# 51.net
KiCad netlist of a schematic drawn in EasyEDA Pro
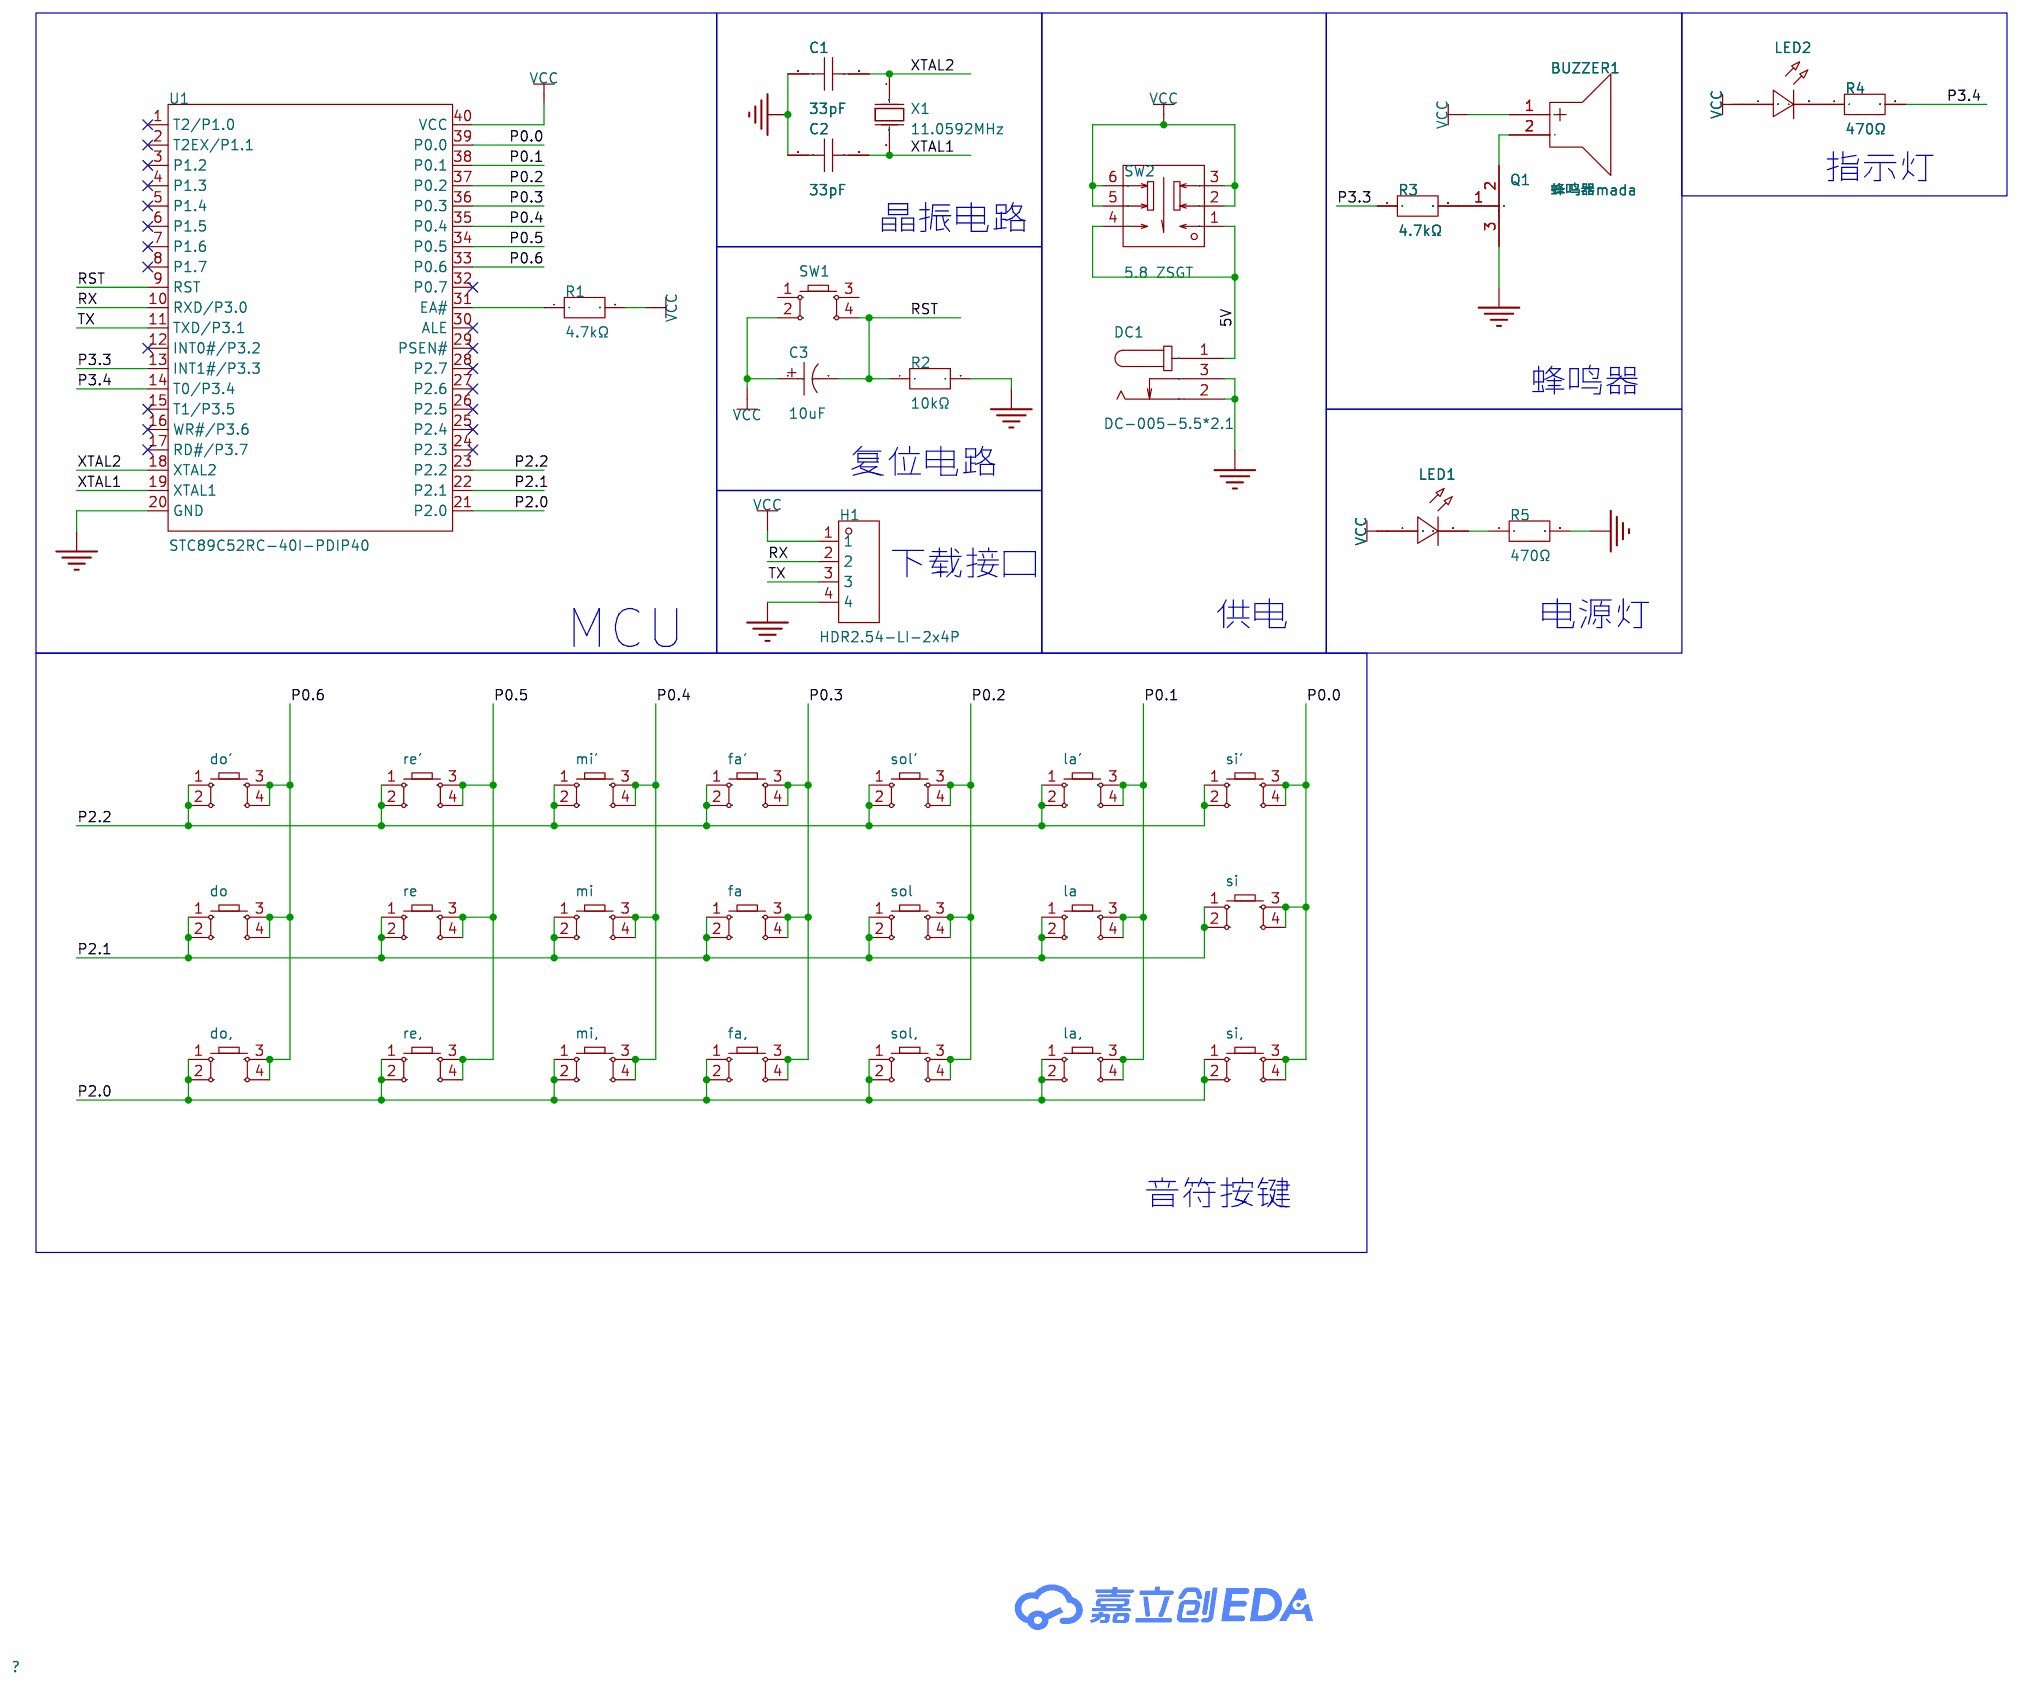
[diagram p0: schematic sheet]

(export (version "E")
  (design (tool "Eeschema 10.0.6"))
  (components
    (comp (ref "BUZZER1")
      (value "蜂鸣器mada")
      (footprint "easyedapro:BUZ-TH_BD9.2-P5.00-D0.6-L-FD")
      (libsource (lib "easyedapro") (part "蜂鸣器MADA"))
    )
    (comp (ref "C1")
      (value "33pF")
      (footprint "easyedapro:CAP-TH_L5.5-W5.0-P5.00-D0.6")
      (description "容值:33pF;精度:±5%;额定电压:2kV;温度系数:SL;")
      (fields (field (name "Manufacturer Part") "CC45SL3DD330JYGNA") (field (name "Manufacturer") "TDK"))
      (libsource (lib "easyedapro") (part "CC45SL3DD330JYGNA"))
    )
    (comp (ref "C2")
      (value "33pF")
      (footprint "easyedapro:CAP-TH_L5.5-W5.0-P5.00-D0.6")
      (description "容值:33pF;精度:±5%;额定电压:2kV;温度系数:SL;")
      (fields (field (name "Manufacturer Part") "CC45SL3DD330JYGNA") (field (name "Manufacturer") "TDK"))
      (libsource (lib "easyedapro") (part "CC45SL3DD330JYGNA"))
    )
    (comp (ref "C3")
      (value "10uF")
      (footprint "easyedapro:CAP-TH_BD5.0-P2.00-D0.5-FD")
      (description "容值:10uF;精度:±20%;额定电压:25V;纹波电流:38mA@120Hz;等效串联电阻(ESR):-;")
      (fields
        (field (name "Manufacturer Part") "KM106M025D11RR0VH2FP0")
        (field (name "Manufacturer") "CX(承兴)")
      )
      (libsource (lib "easyedapro") (part "10uF 25V 5*11"))
    )
    (comp (ref "DC1")
      (value "DC-005-5.5*2.1")
      (footprint "easyedapro:DC-IN-TH_DC-005-2")
      (libsource (lib "easyedapro") (part "DC-005-5.5*2.1"))
    )
    (comp (ref "do")
      (value "~")
      (footprint "easyedapro:Key_SMD_12x12x7.3")
      (libsource (lib "easyedapro") (part "轻触按键"))
    )
    (comp (ref "do'")
      (value "~")
      (footprint "easyedapro:Key_SMD_12x12x7.3")
      (libsource (lib "easyedapro") (part "轻触按键"))
    )
    (comp (ref "do,")
      (value "~")
      (footprint "easyedapro:Key_SMD_12x12x7.3")
      (libsource (lib "easyedapro") (part "轻触按键"))
    )
    (comp (ref "fa")
      (value "~")
      (footprint "easyedapro:Key_SMD_12x12x7.3")
      (libsource (lib "easyedapro") (part "轻触按键"))
    )
    (comp (ref "fa'")
      (value "~")
      (footprint "easyedapro:Key_SMD_12x12x7.3")
      (libsource (lib "easyedapro") (part "轻触按键"))
    )
    (comp (ref "fa,")
      (value "~")
      (footprint "easyedapro:Key_SMD_12x12x7.3")
      (libsource (lib "easyedapro") (part "轻触按键"))
    )
    (comp (ref "H1")
      (value "HDR2.54-LI-2x4P")
      (footprint "easyedapro:HDR-TH_4P-P2.54-V-M")
      (libsource (lib "easyedapro") (part "HDR2.54-LI-2X4P"))
    )
    (comp (ref "la")
      (value "~")
      (footprint "easyedapro:Key_SMD_12x12x7.3")
      (libsource (lib "easyedapro") (part "轻触按键"))
    )
    (comp (ref "la'")
      (value "~")
      (footprint "easyedapro:Key_SMD_12x12x7.3")
      (libsource (lib "easyedapro") (part "轻触按键"))
    )
    (comp (ref "la,")
      (value "~")
      (footprint "easyedapro:Key_SMD_12x12x7.3")
      (libsource (lib "easyedapro") (part "轻触按键"))
    )
    (comp (ref "LED1")
      (value "~")
      (footprint "easyedapro:LED_TH-3mm")
      (libsource (lib "easyedapro") (part "LED_TH-R"))
    )
    (comp (ref "LED2")
      (value "~")
      (footprint "easyedapro:LED_TH-3mm")
      (libsource (lib "easyedapro") (part "LED_TH-R"))
    )
    (comp (ref "mi")
      (value "~")
      (footprint "easyedapro:Key_SMD_12x12x7.3")
      (libsource (lib "easyedapro") (part "轻触按键"))
    )
    (comp (ref "mi'")
      (value "~")
      (footprint "easyedapro:Key_SMD_12x12x7.3")
      (libsource (lib "easyedapro") (part "轻触按键"))
    )
    (comp (ref "mi,")
      (value "~")
      (footprint "easyedapro:Key_SMD_12x12x7.3")
      (libsource (lib "easyedapro") (part "轻触按键"))
    )
    (comp (ref "Q1") (value "~") (footprint "easyedapro:宽三极管") (libsource (lib "easyedapro") (part "宽三极管")))
    (comp (ref "R1")
      (value "4.7kΩ")
      (footprint "easyedapro:RES-TH_BD2.2-L6.5-P10.50-D0.6")
      (description "电阻类型:金属膜电阻;阻值:4.7kΩ;精度:±1%;功率:250mW;温度系数:±50ppm/°C;")
      (fields
        (field (name "Manufacturer Part") "MF0W4FF4701A50")
        (field (name "Manufacturer") "UNI-ROYAL(厚声)")
      )
      (libsource (lib "easyedapro") (part "MF0W4FF4701A50"))
    )
    (comp (ref "R2")
      (value "10kΩ")
      (footprint "easyedapro:RES-TH_BD2.2-L6.5-P10.50-D0.6")
      (description "电阻类型:金属膜电阻;阻值:4.7kΩ;精度:±1%;功率:250mW;温度系数:±50ppm/°C;")
      (fields
        (field (name "Manufacturer Part") "MF0W4FF4701A50")
        (field (name "Manufacturer") "UNI-ROYAL(厚声)")
      )
      (libsource (lib "easyedapro") (part "MF0W4FF4701A50"))
    )
    (comp (ref "R3")
      (value "4.7kΩ")
      (footprint "easyedapro:RES-TH_BD2.2-L6.5-P10.50-D0.6")
      (description "电阻类型:金属膜电阻;阻值:4.7kΩ;精度:±1%;功率:250mW;温度系数:±50ppm/°C;")
      (fields
        (field (name "Manufacturer Part") "MF0W4FF4701A50")
        (field (name "Manufacturer") "UNI-ROYAL(厚声)")
      )
      (libsource (lib "easyedapro") (part "MF0W4FF4701A50"))
    )
    (comp (ref "R4")
      (value "470Ω")
      (footprint "easyedapro:RES-TH_BD2.2-L6.5-P10.50-D0.6")
      (description "电阻类型:金属膜电阻;阻值:470Ω;精度:±1%;功率:250mW;温度系数:±50ppm/°C;")
      (fields
        (field (name "Manufacturer Part") "MF0W4FF4700A50")
        (field (name "Manufacturer") "UNI-ROYAL(厚声)")
      )
      (libsource (lib "easyedapro") (part "MF0W4FF4700A50"))
    )
    (comp (ref "R5")
      (value "470Ω")
      (footprint "easyedapro:RES-TH_BD2.2-L6.5-P10.50-D0.6")
      (description "电阻类型:金属膜电阻;阻值:470Ω;精度:±1%;功率:250mW;温度系数:±50ppm/°C;")
      (fields
        (field (name "Manufacturer Part") "MF0W4FF4700A50")
        (field (name "Manufacturer") "UNI-ROYAL(厚声)")
      )
      (libsource (lib "easyedapro") (part "MF0W4FF4700A50"))
    )
    (comp (ref "re")
      (value "~")
      (footprint "easyedapro:Key_SMD_12x12x7.3")
      (libsource (lib "easyedapro") (part "轻触按键"))
    )
    (comp (ref "re'")
      (value "~")
      (footprint "easyedapro:Key_SMD_12x12x7.3")
      (libsource (lib "easyedapro") (part "轻触按键"))
    )
    (comp (ref "re,")
      (value "~")
      (footprint "easyedapro:Key_SMD_12x12x7.3")
      (libsource (lib "easyedapro") (part "轻触按键"))
    )
    (comp (ref "si")
      (value "~")
      (footprint "easyedapro:Key_SMD_12x12x7.3")
      (libsource (lib "easyedapro") (part "轻触按键"))
    )
    (comp (ref "si'")
      (value "~")
      (footprint "easyedapro:Key_SMD_12x12x7.3")
      (libsource (lib "easyedapro") (part "轻触按键"))
    )
    (comp (ref "si,")
      (value "~")
      (footprint "easyedapro:Key_SMD_12x12x7.3")
      (libsource (lib "easyedapro") (part "轻触按键"))
    )
    (comp (ref "sol")
      (value "~")
      (footprint "easyedapro:Key_SMD_12x12x7.3")
      (libsource (lib "easyedapro") (part "轻触按键"))
    )
    (comp (ref "sol'")
      (value "~")
      (footprint "easyedapro:Key_SMD_12x12x7.3")
      (libsource (lib "easyedapro") (part "轻触按键"))
    )
    (comp (ref "sol,")
      (value "~")
      (footprint "easyedapro:Key_SMD_12x12x7.3")
      (libsource (lib "easyedapro") (part "轻触按键"))
    )
    (comp (ref "SW1")
      (value "~")
      (footprint "easyedapro:Key_SMD_12x12x7.3")
      (libsource (lib "easyedapro") (part "轻触按键"))
    )
    (comp (ref "SW2")
      (value "5.8 ZSGT")
      (footprint "easyedapro:SW-TH_5.8ZSGT")
      (description "电路结构:双刀双掷;自锁/无锁:自锁;安装方式:直插;触点电流:110mA;额定电压 (DC):30V;带灯:不带;作用力:1.5N;机械寿命:10万次;")
      (fields (field (name "Manufacturer") "SHOU HAN(首韩)"))
      (libsource (lib "easyedapro") (part "5.8 ZSGT"))
    )
    (comp (ref "U1")
      (value "STC89C52RC-40I-PDIP40")
      (footprint "easyedapro:DIP-40_L52.0-W13.7-P2.54-LS15.2-BL")
      (description "CPU内核:51系列;应用领域:-;")
      (fields (field (name "Manufacturer") "STC"))
      (libsource (lib "easyedapro") (part "STC89C52RC-40I"))
    )
    (comp (ref "X1")
      (value "11.0592MHz")
      (footprint "easyedapro:HC-49US_L11.5-W4.5-P4.88")
      (description "晶振类型:直插晶振;频率:11.0592MHz;常温频差:±20ppm;负载电容:20pF;频率稳定度:±30ppm;")
      (fields
        (field (name "Manufacturer Part") "X49SD110592MSD2SC")
        (field (name "Manufacturer") "YXC(扬兴晶振)")
      )
      (libsource (lib "easyedapro") (part "X49SD110592MSD2SC"))
    )
  )
  (nets
    (net (code "1") (name "/5V") (class "Default")
      (node (ref "DC1") (pin "1") (pinfunction "1_1") (pintype "unspecified"))
      (node (ref "SW2") (pin "1") (pinfunction "1_1") (pintype "unspecified"))
      (node (ref "SW2") (pin "4") (pinfunction "4_4") (pintype "unspecified"))
    )
    (net (code "2") (name "/P0.0") (class "Default")
      (node (ref "U1") (pin "39") (pinfunction "P0.0_39") (pintype "unspecified"))
      (node (ref "si") (pin "3") (pinfunction "3_3") (pintype "input"))
      (node (ref "si") (pin "4") (pinfunction "4_4") (pintype "input"))
      (node (ref "si'") (pin "3") (pinfunction "3_3") (pintype "input"))
      (node (ref "si'") (pin "4") (pinfunction "4_4") (pintype "input"))
      (node (ref "si,") (pin "3") (pinfunction "3_3") (pintype "input"))
      (node (ref "si,") (pin "4") (pinfunction "4_4") (pintype "input"))
    )
    (net (code "3") (name "/P0.1") (class "Default")
      (node (ref "U1") (pin "38") (pinfunction "P0.1_38") (pintype "unspecified"))
      (node (ref "la") (pin "3") (pinfunction "3_3") (pintype "input"))
      (node (ref "la") (pin "4") (pinfunction "4_4") (pintype "input"))
      (node (ref "la'") (pin "3") (pinfunction "3_3") (pintype "input"))
      (node (ref "la'") (pin "4") (pinfunction "4_4") (pintype "input"))
      (node (ref "la,") (pin "3") (pinfunction "3_3") (pintype "input"))
      (node (ref "la,") (pin "4") (pinfunction "4_4") (pintype "input"))
    )
    (net (code "4") (name "/P0.2") (class "Default")
      (node (ref "U1") (pin "37") (pinfunction "P0.2_37") (pintype "unspecified"))
      (node (ref "sol") (pin "3") (pinfunction "3_3") (pintype "input"))
      (node (ref "sol") (pin "4") (pinfunction "4_4") (pintype "input"))
      (node (ref "sol'") (pin "3") (pinfunction "3_3") (pintype "input"))
      (node (ref "sol'") (pin "4") (pinfunction "4_4") (pintype "input"))
      (node (ref "sol,") (pin "3") (pinfunction "3_3") (pintype "input"))
      (node (ref "sol,") (pin "4") (pinfunction "4_4") (pintype "input"))
    )
    (net (code "5") (name "/P0.3") (class "Default")
      (node (ref "U1") (pin "36") (pinfunction "P0.3_36") (pintype "unspecified"))
      (node (ref "fa") (pin "3") (pinfunction "3_3") (pintype "input"))
      (node (ref "fa") (pin "4") (pinfunction "4_4") (pintype "input"))
      (node (ref "fa'") (pin "3") (pinfunction "3_3") (pintype "input"))
      (node (ref "fa'") (pin "4") (pinfunction "4_4") (pintype "input"))
      (node (ref "fa,") (pin "3") (pinfunction "3_3") (pintype "input"))
      (node (ref "fa,") (pin "4") (pinfunction "4_4") (pintype "input"))
    )
    (net (code "6") (name "/P0.4") (class "Default")
      (node (ref "U1") (pin "35") (pinfunction "P0.4_35") (pintype "unspecified"))
      (node (ref "mi") (pin "3") (pinfunction "3_3") (pintype "input"))
      (node (ref "mi") (pin "4") (pinfunction "4_4") (pintype "input"))
      (node (ref "mi'") (pin "3") (pinfunction "3_3") (pintype "input"))
      (node (ref "mi'") (pin "4") (pinfunction "4_4") (pintype "input"))
      (node (ref "mi,") (pin "3") (pinfunction "3_3") (pintype "input"))
      (node (ref "mi,") (pin "4") (pinfunction "4_4") (pintype "input"))
    )
    (net (code "7") (name "/P0.5") (class "Default")
      (node (ref "U1") (pin "34") (pinfunction "P0.5_34") (pintype "unspecified"))
      (node (ref "re") (pin "3") (pinfunction "3_3") (pintype "input"))
      (node (ref "re") (pin "4") (pinfunction "4_4") (pintype "input"))
      (node (ref "re'") (pin "3") (pinfunction "3_3") (pintype "input"))
      (node (ref "re'") (pin "4") (pinfunction "4_4") (pintype "input"))
      (node (ref "re,") (pin "3") (pinfunction "3_3") (pintype "input"))
      (node (ref "re,") (pin "4") (pinfunction "4_4") (pintype "input"))
    )
    (net (code "8") (name "/P0.6") (class "Default")
      (node (ref "U1") (pin "33") (pinfunction "P0.6_33") (pintype "unspecified"))
      (node (ref "do") (pin "3") (pinfunction "3_3") (pintype "input"))
      (node (ref "do") (pin "4") (pinfunction "4_4") (pintype "input"))
      (node (ref "do'") (pin "3") (pinfunction "3_3") (pintype "input"))
      (node (ref "do'") (pin "4") (pinfunction "4_4") (pintype "input"))
      (node (ref "do,") (pin "3") (pinfunction "3_3") (pintype "input"))
      (node (ref "do,") (pin "4") (pinfunction "4_4") (pintype "input"))
    )
    (net (code "9") (name "/P2.0") (class "Default")
      (node (ref "U1") (pin "21") (pinfunction "P2.0_21") (pintype "unspecified"))
      (node (ref "do,") (pin "1") (pinfunction "1_1") (pintype "input"))
      (node (ref "do,") (pin "2") (pinfunction "2_2") (pintype "input"))
      (node (ref "fa,") (pin "1") (pinfunction "1_1") (pintype "input"))
      (node (ref "fa,") (pin "2") (pinfunction "2_2") (pintype "input"))
      (node (ref "la,") (pin "1") (pinfunction "1_1") (pintype "input"))
      (node (ref "la,") (pin "2") (pinfunction "2_2") (pintype "input"))
      (node (ref "mi,") (pin "1") (pinfunction "1_1") (pintype "input"))
      (node (ref "mi,") (pin "2") (pinfunction "2_2") (pintype "input"))
      (node (ref "re,") (pin "1") (pinfunction "1_1") (pintype "input"))
      (node (ref "re,") (pin "2") (pinfunction "2_2") (pintype "input"))
      (node (ref "si,") (pin "1") (pinfunction "1_1") (pintype "input"))
      (node (ref "si,") (pin "2") (pinfunction "2_2") (pintype "input"))
      (node (ref "sol,") (pin "1") (pinfunction "1_1") (pintype "input"))
      (node (ref "sol,") (pin "2") (pinfunction "2_2") (pintype "input"))
    )
    (net (code "10") (name "/P2.1") (class "Default")
      (node (ref "U1") (pin "22") (pinfunction "P2.1_22") (pintype "unspecified"))
      (node (ref "do") (pin "1") (pinfunction "1_1") (pintype "input"))
      (node (ref "do") (pin "2") (pinfunction "2_2") (pintype "input"))
      (node (ref "fa") (pin "1") (pinfunction "1_1") (pintype "input"))
      (node (ref "fa") (pin "2") (pinfunction "2_2") (pintype "input"))
      (node (ref "la") (pin "1") (pinfunction "1_1") (pintype "input"))
      (node (ref "la") (pin "2") (pinfunction "2_2") (pintype "input"))
      (node (ref "mi") (pin "1") (pinfunction "1_1") (pintype "input"))
      (node (ref "mi") (pin "2") (pinfunction "2_2") (pintype "input"))
      (node (ref "re") (pin "1") (pinfunction "1_1") (pintype "input"))
      (node (ref "re") (pin "2") (pinfunction "2_2") (pintype "input"))
      (node (ref "si") (pin "1") (pinfunction "1_1") (pintype "input"))
      (node (ref "si") (pin "2") (pinfunction "2_2") (pintype "input"))
      (node (ref "sol") (pin "1") (pinfunction "1_1") (pintype "input"))
      (node (ref "sol") (pin "2") (pinfunction "2_2") (pintype "input"))
    )
    (net (code "11") (name "/P2.2") (class "Default")
      (node (ref "U1") (pin "23") (pinfunction "P2.2_23") (pintype "unspecified"))
      (node (ref "do'") (pin "1") (pinfunction "1_1") (pintype "input"))
      (node (ref "do'") (pin "2") (pinfunction "2_2") (pintype "input"))
      (node (ref "fa'") (pin "1") (pinfunction "1_1") (pintype "input"))
      (node (ref "fa'") (pin "2") (pinfunction "2_2") (pintype "input"))
      (node (ref "la'") (pin "1") (pinfunction "1_1") (pintype "input"))
      (node (ref "la'") (pin "2") (pinfunction "2_2") (pintype "input"))
      (node (ref "mi'") (pin "1") (pinfunction "1_1") (pintype "input"))
      (node (ref "mi'") (pin "2") (pinfunction "2_2") (pintype "input"))
      (node (ref "re'") (pin "1") (pinfunction "1_1") (pintype "input"))
      (node (ref "re'") (pin "2") (pinfunction "2_2") (pintype "input"))
      (node (ref "si'") (pin "1") (pinfunction "1_1") (pintype "input"))
      (node (ref "si'") (pin "2") (pinfunction "2_2") (pintype "input"))
      (node (ref "sol'") (pin "1") (pinfunction "1_1") (pintype "input"))
      (node (ref "sol'") (pin "2") (pinfunction "2_2") (pintype "input"))
    )
    (net (code "12") (name "/P3.3") (class "Default")
      (node (ref "R3") (pin "1") (pinfunction "1_1") (pintype "unspecified"))
      (node (ref "U1") (pin "13") (pinfunction "INT1#/P3.3_13") (pintype "unspecified"))
    )
    (net (code "13") (name "/P3.4") (class "Default")
      (node (ref "R4") (pin "2") (pinfunction "2_2") (pintype "unspecified"))
      (node (ref "U1") (pin "14") (pinfunction "T0/P3.4_14") (pintype "unspecified"))
    )
    (net (code "14") (name "/RST") (class "Default")
      (node (ref "C3") (pin "2") (pinfunction "2_2") (pintype "input"))
      (node (ref "R2") (pin "1") (pinfunction "1_1") (pintype "unspecified"))
      (node (ref "SW1") (pin "4") (pinfunction "4_4") (pintype "input"))
      (node (ref "U1") (pin "9") (pinfunction "RST_9") (pintype "unspecified"))
    )
    (net (code "15") (name "/RX") (class "Default")
      (node (ref "H1") (pin "2") (pinfunction "2_2") (pintype "unspecified"))
      (node (ref "U1") (pin "10") (pinfunction "RXD/P3.0_10") (pintype "unspecified"))
    )
    (net (code "16") (name "/TX") (class "Default")
      (node (ref "H1") (pin "3") (pinfunction "3_3") (pintype "unspecified"))
      (node (ref "U1") (pin "11") (pinfunction "TXD/P3.1_11") (pintype "unspecified"))
    )
    (net (code "17") (name "/XTAL1") (class "Default")
      (node (ref "C2") (pin "2") (pinfunction "2_2") (pintype "unspecified"))
      (node (ref "U1") (pin "19") (pinfunction "XTAL1_19") (pintype "unspecified"))
      (node (ref "X1") (pin "2") (pinfunction "OSC2_2") (pintype "input"))
    )
    (net (code "18") (name "/XTAL2") (class "Default")
      (node (ref "C1") (pin "2") (pinfunction "2_2") (pintype "unspecified"))
      (node (ref "U1") (pin "18") (pinfunction "XTAL2_18") (pintype "unspecified"))
      (node (ref "X1") (pin "1") (pinfunction "OSC1_1") (pintype "input"))
    )
    (net (code "19") (name "GND") (class "Default")
      (node (ref "C1") (pin "1") (pinfunction "1_1") (pintype "unspecified"))
      (node (ref "C2") (pin "1") (pinfunction "1_1") (pintype "unspecified"))
      (node (ref "DC1") (pin "2") (pinfunction "2_2") (pintype "unspecified"))
      (node (ref "DC1") (pin "3") (pinfunction "3_3") (pintype "unspecified"))
      (node (ref "H1") (pin "4") (pinfunction "4_4") (pintype "unspecified"))
      (node (ref "Q1") (pin "3") (pinfunction "3_3") (pintype "input"))
      (node (ref "R2") (pin "2") (pinfunction "2_2") (pintype "unspecified"))
      (node (ref "R5") (pin "2") (pinfunction "2_2") (pintype "unspecified"))
      (node (ref "U1") (pin "20") (pinfunction "GND_20") (pintype "unspecified"))
    )
    (net (code "20") (name "Net-(BUZZER1--)") (class "Default")
      (node (ref "BUZZER1") (pin "2") (pinfunction "-_2") (pintype "unspecified"))
      (node (ref "Q1") (pin "2") (pinfunction "2_2") (pintype "input"))
    )
    (net (code "21") (name "Net-(LED1-A)") (class "Default")
      (node (ref "LED1") (pin "2") (pinfunction "A_2") (pintype "input"))
      (node (ref "R5") (pin "1") (pinfunction "1_1") (pintype "unspecified"))
    )
    (net (code "22") (name "Net-(LED2-A)") (class "Default")
      (node (ref "LED2") (pin "2") (pinfunction "A_2") (pintype "input"))
      (node (ref "R4") (pin "1") (pinfunction "1_1") (pintype "unspecified"))
    )
    (net (code "23") (name "Net-(Q1-Pad1)") (class "Default")
      (node (ref "Q1") (pin "1") (pinfunction "1_1") (pintype "input"))
      (node (ref "R3") (pin "2") (pinfunction "2_2") (pintype "unspecified"))
    )
    (net (code "24") (name "Net-(U1-EA#)") (class "Default")
      (node (ref "R1") (pin "1") (pinfunction "1_1") (pintype "unspecified"))
      (node (ref "U1") (pin "31") (pinfunction "EA#_31") (pintype "unspecified"))
    )
    (net (code "25") (name "VCC") (class "Default")
      (node (ref "BUZZER1") (pin "1") (pinfunction "+_1") (pintype "unspecified"))
      (node (ref "C3") (pin "1") (pinfunction "1_1") (pintype "input"))
      (node (ref "H1") (pin "1") (pinfunction "1_1") (pintype "unspecified"))
      (node (ref "LED1") (pin "1") (pinfunction "C_1") (pintype "input"))
      (node (ref "LED2") (pin "1") (pinfunction "C_1") (pintype "input"))
      (node (ref "R1") (pin "2") (pinfunction "2_2") (pintype "unspecified"))
      (node (ref "SW1") (pin "2") (pinfunction "2_2") (pintype "input"))
      (node (ref "SW2") (pin "2") (pinfunction "2_2") (pintype "unspecified"))
      (node (ref "SW2") (pin "3") (pinfunction "3_3") (pintype "unspecified"))
      (node (ref "SW2") (pin "5") (pinfunction "5_5") (pintype "unspecified"))
      (node (ref "SW2") (pin "6") (pinfunction "6_6") (pintype "unspecified"))
      (node (ref "U1") (pin "40") (pinfunction "VCC_40") (pintype "unspecified"))
    )
    (net (code "26") (name "unconnected-(SW1-Pad1)") (class "Default")
      (node (ref "SW1") (pin "1") (pinfunction "1_1") (pintype "input"))
    )
    (net (code "27") (name "unconnected-(SW1-Pad3)") (class "Default")
      (node (ref "SW1") (pin "3") (pinfunction "3_3") (pintype "input"))
    )
    (net (code "28") (name "unconnected-(U1-ALE-Pad30)") (class "Default")
      (node (ref "U1") (pin "30") (pinfunction "ALE_30") (pintype "unspecified+no_connect"))
    )
    (net (code "29") (name "unconnected-(U1-INT0#{slash}P3.2-Pad12)") (class "Default")
      (node (ref "U1") (pin "12") (pinfunction "INT0#/P3.2_12") (pintype "unspecified+no_connect"))
    )
    (net (code "30") (name "unconnected-(U1-P0.7-Pad32)") (class "Default")
      (node (ref "U1") (pin "32") (pinfunction "P0.7_32") (pintype "unspecified+no_connect"))
    )
    (net (code "31") (name "unconnected-(U1-P1.2-Pad3)") (class "Default")
      (node (ref "U1") (pin "3") (pinfunction "P1.2_3") (pintype "unspecified+no_connect"))
    )
    (net (code "32") (name "unconnected-(U1-P1.3-Pad4)") (class "Default")
      (node (ref "U1") (pin "4") (pinfunction "P1.3_4") (pintype "unspecified+no_connect"))
    )
    (net (code "33") (name "unconnected-(U1-P1.4-Pad5)") (class "Default")
      (node (ref "U1") (pin "5") (pinfunction "P1.4_5") (pintype "unspecified+no_connect"))
    )
    (net (code "34") (name "unconnected-(U1-P1.5-Pad6)") (class "Default")
      (node (ref "U1") (pin "6") (pinfunction "P1.5_6") (pintype "unspecified+no_connect"))
    )
    (net (code "35") (name "unconnected-(U1-P1.6-Pad7)") (class "Default")
      (node (ref "U1") (pin "7") (pinfunction "P1.6_7") (pintype "unspecified+no_connect"))
    )
    (net (code "36") (name "unconnected-(U1-P1.7-Pad8)") (class "Default")
      (node (ref "U1") (pin "8") (pinfunction "P1.7_8") (pintype "unspecified+no_connect"))
    )
    (net (code "37") (name "unconnected-(U1-P2.3-Pad24)") (class "Default")
      (node (ref "U1") (pin "24") (pinfunction "P2.3_24") (pintype "unspecified+no_connect"))
    )
    (net (code "38") (name "unconnected-(U1-P2.4-Pad25)") (class "Default")
      (node (ref "U1") (pin "25") (pinfunction "P2.4_25") (pintype "unspecified+no_connect"))
    )
    (net (code "39") (name "unconnected-(U1-P2.5-Pad26)") (class "Default")
      (node (ref "U1") (pin "26") (pinfunction "P2.5_26") (pintype "unspecified+no_connect"))
    )
    (net (code "40") (name "unconnected-(U1-P2.6-Pad27)") (class "Default")
      (node (ref "U1") (pin "27") (pinfunction "P2.6_27") (pintype "unspecified+no_connect"))
    )
    (net (code "41") (name "unconnected-(U1-P2.7-Pad28)") (class "Default")
      (node (ref "U1") (pin "28") (pinfunction "P2.7_28") (pintype "unspecified+no_connect"))
    )
    (net (code "42") (name "unconnected-(U1-PSEN#-Pad29)") (class "Default")
      (node (ref "U1") (pin "29") (pinfunction "PSEN#_29") (pintype "unspecified+no_connect"))
    )
    (net (code "43") (name "unconnected-(U1-RD#{slash}P3.7-Pad17)") (class "Default")
      (node (ref "U1") (pin "17") (pinfunction "RD#/P3.7_17") (pintype "unspecified+no_connect"))
    )
    (net (code "44") (name "unconnected-(U1-T1{slash}P3.5-Pad15)") (class "Default")
      (node (ref "U1") (pin "15") (pinfunction "T1/P3.5_15") (pintype "unspecified+no_connect"))
    )
    (net (code "45") (name "unconnected-(U1-T2EX{slash}P1.1-Pad2)") (class "Default")
      (node (ref "U1") (pin "2") (pinfunction "T2EX/P1.1_2") (pintype "unspecified+no_connect"))
    )
    (net (code "46") (name "unconnected-(U1-T2{slash}P1.0-Pad1)") (class "Default")
      (node (ref "U1") (pin "1") (pinfunction "T2/P1.0_1") (pintype "unspecified+no_connect"))
    )
    (net (code "47") (name "unconnected-(U1-WR#{slash}P3.6-Pad16)") (class "Default")
      (node (ref "U1") (pin "16") (pinfunction "WR#/P3.6_16") (pintype "unspecified+no_connect"))
    )
  )
)
